# LVDS.net
KiCad netlist of a schematic drawn in Altium Designer
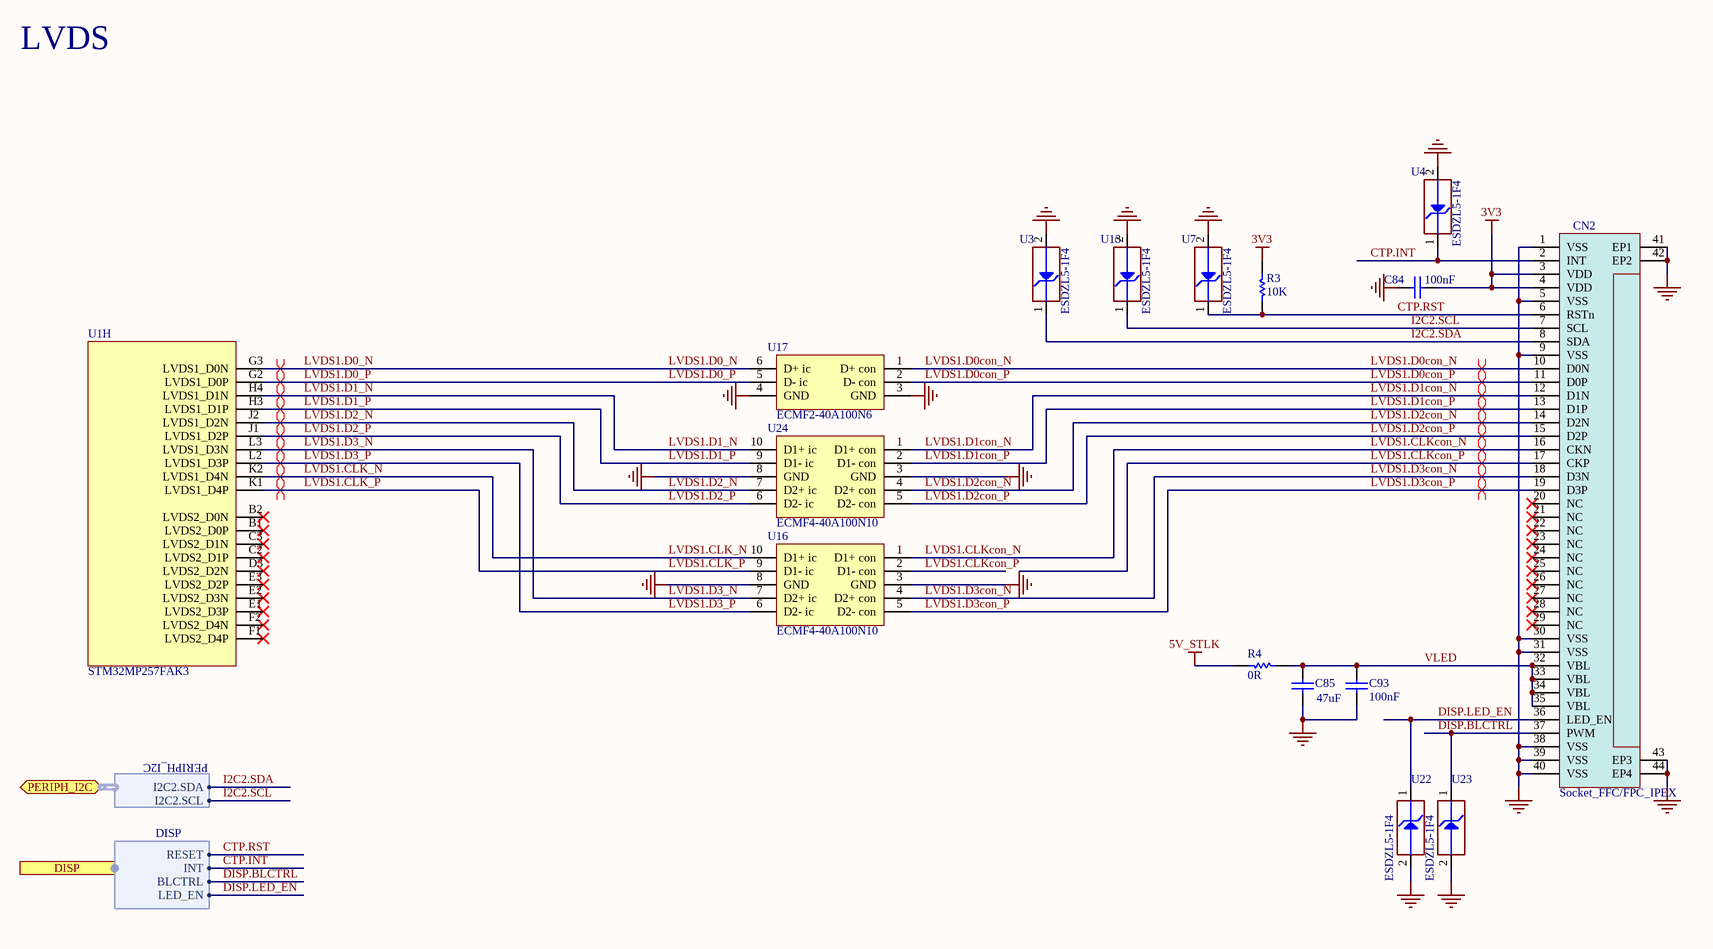
[diagram p0: LVDS.SchDoc]

(export (version "E")
  (design (tool "Eeschema 10.0.6"))
  (components
    (comp (ref "C84")
      (value "100nF")
      (footprint "C0402")
      (description "Capacitor, MLCC, 100nF, 10V, X5R, +/-10%, 0402, T=0,5mm")
      (fields (field (name "INTERNAL_PART_NUMBER") "MCD-02352") (field (name "MANUFACTURER") "YAGEO"))
      (libsource (lib "MCD_PARTS_database") (part "Capacitor"))
    )
    (comp (ref "C85")
      (value "47uF")
      (footprint "C0805")
      (description "Capacitor, MLCC, 47uF, 10V, X5R, +/-20%, 0805, T=1.25mm")
      (fields (field (name "INTERNAL_PART_NUMBER") "MCD-00204") (field (name "MANUFACTURER") "MURATA"))
      (libsource (lib "MCD_PARTS_database") (part "Capacitor"))
    )
    (comp (ref "C93")
      (value "100nF")
      (footprint "C0402")
      (description "Capacitor, MLCC, 100nF, 10V, X5R, +/-10%, 0402, T=0,5mm")
      (fields (field (name "INTERNAL_PART_NUMBER") "MCD-02352") (field (name "MANUFACTURER") "YAGEO"))
      (libsource (lib "MCD_PARTS_database") (part "Capacitor"))
    )
    (comp (ref "CN2")
      (value "Socket_FFC/FPC_IPEX")
      (footprint "CON_I-PEX_20455-040E-76")
      (description "Socket_FFC/FPC, 40pins, 0.5mm, RA, SMD, T=1mm")
      (fields (field (name "INTERNAL_PART_NUMBER") "MCD-03562") (field (name "MANUFACTURER") "I-PEX"))
      (libsource (lib "MCD_PARTS_database") (part "IPEX20455"))
    )
    (comp (ref "R3")
      (value "10K")
      (footprint "R0402")
      (description "Resistor, 10K, 0402, +/-1%, 1/16W")
      (fields (field (name "INTERNAL_PART_NUMBER") "MCD-00053") (field (name "BMS_PART_NUMBER") "9131590"))
      (libsource (lib "MCD_PARTS_database") (part "Resistor"))
    )
    (comp (ref "R4")
      (value "0R")
      (footprint "R0805")
      (description "Resistor, 0R, 0805, +/-5%, 1/8W")
      (fields (field (name "INTERNAL_PART_NUMBER") "MCD-00179") (field (name "MANUFACTURER") "YAGEO"))
      (libsource (lib "MCD_PARTS_database") (part "Resistor"))
    )
    (comp (ref "U1")
      (value "STM32MP257FAK3")
      (footprint "ICC_TFBGA424_14X14_P050_H1P20_CODE-B0A2")
      (description "MPU , 2xCortex-A35@1.5GHz, Cortex-M33@400MHz, TFBGA 14x14, pitch 0.5, 648KB SRAM, With Crypto")
      (fields
        (field (name "INTERNAL_PART_NUMBER") "MCD-03375")
        (field (name "MANUFACTURER") "STMICROELECTRONICS")
      )
      (libsource (lib "MCD_PARTS_database") (part "STM32MP257FAK3"))
    )
    (comp (ref "U3")
      (value "ESDZL5-1F4")
      (footprint "ESD_ST0201")
      (description "ESD protection , 0201")
      (fields
        (field (name "INTERNAL_PART_NUMBER") "MCD-03501")
        (field (name "MANUFACTURER") "STMICROELECTRONICS")
      )
      (libsource (lib "") (part "ESD-TRANSIL_1"))
    )
    (comp (ref "U4")
      (value "ESDZL5-1F4")
      (footprint "ESD_ST0201")
      (description "ESD protection , 0201")
      (fields
        (field (name "INTERNAL_PART_NUMBER") "MCD-03501")
        (field (name "MANUFACTURER") "STMICROELECTRONICS")
      )
      (libsource (lib "") (part "ESD-TRANSIL_1"))
    )
    (comp (ref "U7")
      (value "ESDZL5-1F4")
      (footprint "ESD_ST0201")
      (description "ESD protection , 0201")
      (fields
        (field (name "INTERNAL_PART_NUMBER") "MCD-03501")
        (field (name "MANUFACTURER") "STMICROELECTRONICS")
      )
      (libsource (lib "") (part "ESD-TRANSIL_1"))
    )
    (comp (ref "U13")
      (value "ESDZL5-1F4")
      (footprint "ESD_ST0201")
      (description "ESD protection , 0201")
      (fields
        (field (name "INTERNAL_PART_NUMBER") "MCD-03501")
        (field (name "MANUFACTURER") "STMICROELECTRONICS")
      )
      (libsource (lib "") (part "ESD-TRANSIL_1"))
    )
    (comp (ref "U16")
      (value "ECMF4-40A100N10")
      (footprint "ESD_UQFN-10L_2P25X1P4_P040")
      (description "ESD protection & Common Filter High Speed serial Interfaces , 0.4 pitch")
      (fields
        (field (name "INTERNAL_PART_NUMBER") "MCD-03059")
        (field (name "MANUFACTURER") "STMICROELECTRONICS")
      )
      (libsource (lib "MCD_PARTS_database") (part "ECMF4-40A100N10"))
    )
    (comp (ref "U17")
      (value "ECMF2-40A100N6")
      (footprint "ESD_UQFN-6L_1P45X1P4_P040")
      (description "ESD protection & Common Filter High Speed serial Interfaces , 0.4 pitch")
      (fields
        (field (name "INTERNAL_PART_NUMBER") "MCD-03060")
        (field (name "MANUFACTURER") "STMICROELECTRONICS")
      )
      (libsource (lib "MCD_PARTS_database") (part "ECMF2-40A100N6"))
    )
    (comp (ref "U22")
      (value "ESDZL5-1F4")
      (footprint "ESD_ST0201")
      (description "ESD protection , 0201")
      (fields
        (field (name "INTERNAL_PART_NUMBER") "MCD-03501")
        (field (name "MANUFACTURER") "STMICROELECTRONICS")
      )
      (libsource (lib "MCD_PARTS_database") (part "ESD-TRANSIL"))
    )
    (comp (ref "U23")
      (value "ESDZL5-1F4")
      (footprint "ESD_ST0201")
      (description "ESD protection , 0201")
      (fields
        (field (name "INTERNAL_PART_NUMBER") "MCD-03501")
        (field (name "MANUFACTURER") "STMICROELECTRONICS")
      )
      (libsource (lib "MCD_PARTS_database") (part "ESD-TRANSIL"))
    )
    (comp (ref "U24")
      (value "ECMF4-40A100N10")
      (footprint "ESD_UQFN-10L_2P25X1P4_P040")
      (description "ESD protection & Common Filter High Speed serial Interfaces , 0.4 pitch")
      (fields
        (field (name "INTERNAL_PART_NUMBER") "MCD-03059")
        (field (name "MANUFACTURER") "STMICROELECTRONICS")
      )
      (libsource (lib "MCD_PARTS_database") (part "ECMF4-40A100N10"))
    )
  )
  (nets
    (net (code "3") (name "/CTP.INT") (class "Default")
      (node (ref "CN2") (pin "2") (pinfunction "INT_2") (pintype "passive"))
      (node (ref "U4") (pin "1") (pinfunction "IO1_1") (pintype "passive"))
    )
    (net (code "4") (name "/CTP.RST") (class "Default")
      (node (ref "CN2") (pin "6") (pinfunction "RSTn_6") (pintype "passive"))
      (node (ref "R3") (pin "2") (pinfunction "2_2") (pintype "passive"))
      (node (ref "U7") (pin "1") (pinfunction "IO1_1") (pintype "passive"))
    )
    (net (code "5") (name "/DISP.BLCTRL") (class "Default")
      (node (ref "CN2") (pin "37") (pinfunction "PWM_37") (pintype "passive"))
      (node (ref "U23") (pin "1") (pinfunction "IO1_1") (pintype "passive"))
    )
    (net (code "6") (name "/DISP.LED_EN") (class "Default")
      (node (ref "CN2") (pin "36") (pinfunction "LED_EN_36") (pintype "passive"))
      (node (ref "U22") (pin "1") (pinfunction "IO1_1") (pintype "passive"))
    )
    (net (code "7") (name "/I2C2.SCL") (class "Default")
      (node (ref "CN2") (pin "7") (pinfunction "SCL_7") (pintype "passive"))
      (node (ref "U13") (pin "1") (pinfunction "IO1_1") (pintype "passive"))
    )
    (net (code "8") (name "/I2C2.SDA") (class "Default")
      (node (ref "CN2") (pin "8") (pinfunction "SDA_8") (pintype "passive"))
      (node (ref "U3") (pin "1") (pinfunction "IO1_1") (pintype "passive"))
    )
    (net (code "9") (name "/LVDS1.CLK_N") (class "Default")
      (node (ref "U1") (pin "K2") (pinfunction "LVDS1_D4N_K2") (pintype "passive"))
      (node (ref "U16") (pin "10") (pinfunction "D1+_ic_10") (pintype "passive"))
    )
    (net (code "10") (name "/LVDS1.CLK_P") (class "Default")
      (node (ref "U1") (pin "K1") (pinfunction "LVDS1_D4P_K1") (pintype "passive"))
      (node (ref "U16") (pin "9") (pinfunction "D1-_ic_9") (pintype "passive"))
    )
    (net (code "11") (name "/LVDS1.CLKcon_N") (class "Default")
      (node (ref "CN2") (pin "16") (pinfunction "CKN_16") (pintype "passive"))
      (node (ref "U16") (pin "1") (pinfunction "D1+_con_1") (pintype "passive"))
    )
    (net (code "12") (name "/LVDS1.CLKcon_P") (class "Default")
      (node (ref "CN2") (pin "17") (pinfunction "CKP_17") (pintype "passive"))
      (node (ref "U16") (pin "2") (pinfunction "D1-_con_2") (pintype "passive"))
    )
    (net (code "13") (name "/LVDS1.D0_N") (class "Default")
      (node (ref "U1") (pin "G3") (pinfunction "LVDS1_D0N_G3") (pintype "passive"))
      (node (ref "U17") (pin "6") (pinfunction "D+_ic_6") (pintype "passive"))
    )
    (net (code "14") (name "/LVDS1.D0_P") (class "Default")
      (node (ref "U1") (pin "G2") (pinfunction "LVDS1_D0P_G2") (pintype "passive"))
      (node (ref "U17") (pin "5") (pinfunction "D-_ic_5") (pintype "passive"))
    )
    (net (code "15") (name "/LVDS1.D0con_N") (class "Default")
      (node (ref "CN2") (pin "10") (pinfunction "D0N_10") (pintype "passive"))
      (node (ref "U17") (pin "1") (pinfunction "D+_con_1") (pintype "passive"))
    )
    (net (code "16") (name "/LVDS1.D0con_P") (class "Default")
      (node (ref "CN2") (pin "11") (pinfunction "D0P_11") (pintype "passive"))
      (node (ref "U17") (pin "2") (pinfunction "D-_con_2") (pintype "passive"))
    )
    (net (code "17") (name "/LVDS1.D1_N") (class "Default")
      (node (ref "U1") (pin "H4") (pinfunction "LVDS1_D1N_H4") (pintype "passive"))
      (node (ref "U24") (pin "10") (pinfunction "D1+_ic_10") (pintype "passive"))
    )
    (net (code "18") (name "/LVDS1.D1_P") (class "Default")
      (node (ref "U1") (pin "H3") (pinfunction "LVDS1_D1P_H3") (pintype "passive"))
      (node (ref "U24") (pin "9") (pinfunction "D1-_ic_9") (pintype "passive"))
    )
    (net (code "19") (name "/LVDS1.D1con_N") (class "Default")
      (node (ref "CN2") (pin "12") (pinfunction "D1N_12") (pintype "passive"))
      (node (ref "U24") (pin "1") (pinfunction "D1+_con_1") (pintype "passive"))
    )
    (net (code "20") (name "/LVDS1.D1con_P") (class "Default")
      (node (ref "CN2") (pin "13") (pinfunction "D1P_13") (pintype "passive"))
      (node (ref "U24") (pin "2") (pinfunction "D1-_con_2") (pintype "passive"))
    )
    (net (code "21") (name "/LVDS1.D2_N") (class "Default")
      (node (ref "U1") (pin "J2") (pinfunction "LVDS1_D2N_J2") (pintype "passive"))
      (node (ref "U24") (pin "7") (pinfunction "D2+_ic_7") (pintype "passive"))
    )
    (net (code "22") (name "/LVDS1.D2_P") (class "Default")
      (node (ref "U1") (pin "J1") (pinfunction "LVDS1_D2P_J1") (pintype "passive"))
      (node (ref "U24") (pin "6") (pinfunction "D2-_ic_6") (pintype "passive"))
    )
    (net (code "23") (name "/LVDS1.D2con_N") (class "Default")
      (node (ref "CN2") (pin "14") (pinfunction "D2N_14") (pintype "passive"))
      (node (ref "U24") (pin "4") (pinfunction "D2+_con_4") (pintype "passive"))
    )
    (net (code "24") (name "/LVDS1.D2con_P") (class "Default")
      (node (ref "CN2") (pin "15") (pinfunction "D2P_15") (pintype "passive"))
      (node (ref "U24") (pin "5") (pinfunction "D2-_con_5") (pintype "passive"))
    )
    (net (code "25") (name "/LVDS1.D3_N") (class "Default")
      (node (ref "U1") (pin "L3") (pinfunction "LVDS1_D3N_L3") (pintype "passive"))
      (node (ref "U16") (pin "7") (pinfunction "D2+_ic_7") (pintype "passive"))
    )
    (net (code "26") (name "/LVDS1.D3_P") (class "Default")
      (node (ref "U1") (pin "L2") (pinfunction "LVDS1_D3P_L2") (pintype "passive"))
      (node (ref "U16") (pin "6") (pinfunction "D2-_ic_6") (pintype "passive"))
    )
    (net (code "27") (name "/LVDS1.D3con_N") (class "Default")
      (node (ref "CN2") (pin "18") (pinfunction "D3N_18") (pintype "passive"))
      (node (ref "U16") (pin "4") (pinfunction "D2+_con_4") (pintype "passive"))
    )
    (net (code "28") (name "/LVDS1.D3con_P") (class "Default")
      (node (ref "CN2") (pin "19") (pinfunction "D3P_19") (pintype "passive"))
      (node (ref "U16") (pin "5") (pinfunction "D2-_con_5") (pintype "passive"))
    )
    (net (code "29") (name "/VLED") (class "Default")
      (node (ref "C85") (pin "2") (pinfunction "2_2") (pintype "passive"))
      (node (ref "C93") (pin "2") (pinfunction "2_2") (pintype "passive"))
      (node (ref "CN2") (pin "32") (pinfunction "VBL_32") (pintype "passive"))
      (node (ref "CN2") (pin "33") (pinfunction "VBL_33") (pintype "passive"))
      (node (ref "CN2") (pin "34") (pinfunction "VBL_34") (pintype "passive"))
      (node (ref "CN2") (pin "35") (pinfunction "VBL_35") (pintype "passive"))
      (node (ref "R4") (pin "1") (pinfunction "1_1") (pintype "passive"))
    )
    (net (code "32") (name "3V3") (class "Default")
      (node (ref "C84") (pin "2") (pinfunction "2_2") (pintype "passive"))
      (node (ref "CN2") (pin "3") (pinfunction "VDD_3") (pintype "passive"))
      (node (ref "CN2") (pin "4") (pinfunction "VDD_4") (pintype "passive"))
      (node (ref "R3") (pin "1") (pinfunction "1_1") (pintype "passive"))
    )
    (net (code "33") (name "5V_STLK") (class "Default")
      (node (ref "R4") (pin "2") (pinfunction "2_2") (pintype "passive"))
    )
    (net (code "34") (name "GND") (class "Default")
      (node (ref "C84") (pin "1") (pinfunction "1_1") (pintype "passive"))
      (node (ref "C85") (pin "1") (pinfunction "1_1") (pintype "passive"))
      (node (ref "C93") (pin "1") (pinfunction "1_1") (pintype "passive"))
      (node (ref "CN2") (pin "1") (pinfunction "VSS_1") (pintype "passive"))
      (node (ref "CN2") (pin "30") (pinfunction "VSS_30") (pintype "passive"))
      (node (ref "CN2") (pin "31") (pinfunction "VSS_31") (pintype "passive"))
      (node (ref "CN2") (pin "38") (pinfunction "VSS_38") (pintype "passive"))
      (node (ref "CN2") (pin "39") (pinfunction "VSS_39") (pintype "passive"))
      (node (ref "CN2") (pin "40") (pinfunction "VSS_40") (pintype "passive"))
      (node (ref "CN2") (pin "41") (pinfunction "EP1_41") (pintype "passive"))
      (node (ref "CN2") (pin "42") (pinfunction "EP2_42") (pintype "passive"))
      (node (ref "CN2") (pin "43") (pinfunction "EP3_43") (pintype "passive"))
      (node (ref "CN2") (pin "44") (pinfunction "EP4_44") (pintype "passive"))
      (node (ref "CN2") (pin "5") (pinfunction "VSS_5") (pintype "passive"))
      (node (ref "CN2") (pin "9") (pinfunction "VSS_9") (pintype "passive"))
      (node (ref "U13") (pin "2") (pinfunction "GND_2") (pintype "passive"))
      (node (ref "U16") (pin "3") (pinfunction "GND_3") (pintype "passive"))
      (node (ref "U16") (pin "8") (pinfunction "GND_8") (pintype "passive"))
      (node (ref "U17") (pin "3") (pinfunction "GND_3") (pintype "passive"))
      (node (ref "U17") (pin "4") (pinfunction "GND_4") (pintype "passive"))
      (node (ref "U22") (pin "2") (pinfunction "GND_2") (pintype "passive"))
      (node (ref "U23") (pin "2") (pinfunction "GND_2") (pintype "passive"))
      (node (ref "U24") (pin "3") (pinfunction "GND_3") (pintype "passive"))
      (node (ref "U24") (pin "8") (pinfunction "GND_8") (pintype "passive"))
      (node (ref "U3") (pin "2") (pinfunction "GND_2") (pintype "passive"))
      (node (ref "U4") (pin "2") (pinfunction "GND_2") (pintype "passive"))
      (node (ref "U7") (pin "2") (pinfunction "GND_2") (pintype "passive"))
    )
    (net (code "35") (name "unconnected-(CN2-NC-Pad20)") (class "Default")
      (node (ref "CN2") (pin "20") (pinfunction "NC_20") (pintype "passive+no_connect"))
    )
    (net (code "36") (name "unconnected-(CN2-NC-Pad21)") (class "Default")
      (node (ref "CN2") (pin "21") (pinfunction "NC_21") (pintype "passive+no_connect"))
    )
    (net (code "37") (name "unconnected-(CN2-NC-Pad22)") (class "Default")
      (node (ref "CN2") (pin "22") (pinfunction "NC_22") (pintype "passive+no_connect"))
    )
    (net (code "38") (name "unconnected-(CN2-NC-Pad23)") (class "Default")
      (node (ref "CN2") (pin "23") (pinfunction "NC_23") (pintype "passive+no_connect"))
    )
    (net (code "39") (name "unconnected-(CN2-NC-Pad24)") (class "Default")
      (node (ref "CN2") (pin "24") (pinfunction "NC_24") (pintype "passive+no_connect"))
    )
    (net (code "40") (name "unconnected-(CN2-NC-Pad25)") (class "Default")
      (node (ref "CN2") (pin "25") (pinfunction "NC_25") (pintype "passive+no_connect"))
    )
    (net (code "41") (name "unconnected-(CN2-NC-Pad26)") (class "Default")
      (node (ref "CN2") (pin "26") (pinfunction "NC_26") (pintype "passive+no_connect"))
    )
    (net (code "42") (name "unconnected-(CN2-NC-Pad27)") (class "Default")
      (node (ref "CN2") (pin "27") (pinfunction "NC_27") (pintype "passive+no_connect"))
    )
    (net (code "43") (name "unconnected-(CN2-NC-Pad28)") (class "Default")
      (node (ref "CN2") (pin "28") (pinfunction "NC_28") (pintype "passive+no_connect"))
    )
    (net (code "44") (name "unconnected-(CN2-NC-Pad29)") (class "Default")
      (node (ref "CN2") (pin "29") (pinfunction "NC_29") (pintype "passive+no_connect"))
    )
    (net (code "45") (name "unconnected-(U1H-LVDS2_D0N-PadB2)") (class "Default")
      (node (ref "U1") (pin "B2") (pinfunction "LVDS2_D0N_B2") (pintype "passive+no_connect"))
    )
    (net (code "46") (name "unconnected-(U1H-LVDS2_D0P-PadB1)") (class "Default")
      (node (ref "U1") (pin "B1") (pinfunction "LVDS2_D0P_B1") (pintype "passive+no_connect"))
    )
    (net (code "47") (name "unconnected-(U1H-LVDS2_D1N-PadC3)") (class "Default")
      (node (ref "U1") (pin "C3") (pinfunction "LVDS2_D1N_C3") (pintype "passive+no_connect"))
    )
    (net (code "48") (name "unconnected-(U1H-LVDS2_D1P-PadC2)") (class "Default")
      (node (ref "U1") (pin "C2") (pinfunction "LVDS2_D1P_C2") (pintype "passive+no_connect"))
    )
    (net (code "49") (name "unconnected-(U1H-LVDS2_D2N-PadD3)") (class "Default")
      (node (ref "U1") (pin "D3") (pinfunction "LVDS2_D2N_D3") (pintype "passive+no_connect"))
    )
    (net (code "50") (name "unconnected-(U1H-LVDS2_D2P-PadE3)") (class "Default")
      (node (ref "U1") (pin "E3") (pinfunction "LVDS2_D2P_E3") (pintype "passive+no_connect"))
    )
    (net (code "51") (name "unconnected-(U1H-LVDS2_D3N-PadE2)") (class "Default")
      (node (ref "U1") (pin "E2") (pinfunction "LVDS2_D3N_E2") (pintype "passive+no_connect"))
    )
    (net (code "52") (name "unconnected-(U1H-LVDS2_D3P-PadE1)") (class "Default")
      (node (ref "U1") (pin "E1") (pinfunction "LVDS2_D3P_E1") (pintype "passive+no_connect"))
    )
    (net (code "53") (name "unconnected-(U1H-LVDS2_D4N-PadF2)") (class "Default")
      (node (ref "U1") (pin "F2") (pinfunction "LVDS2_D4N_F2") (pintype "passive+no_connect"))
    )
    (net (code "54") (name "unconnected-(U1H-LVDS2_D4P-PadF1)") (class "Default")
      (node (ref "U1") (pin "F1") (pinfunction "LVDS2_D4P_F1") (pintype "passive+no_connect"))
    )
  )
)
